# EasyPlanter_V2.net
KiCad netlist of a schematic drawn in EAGLE
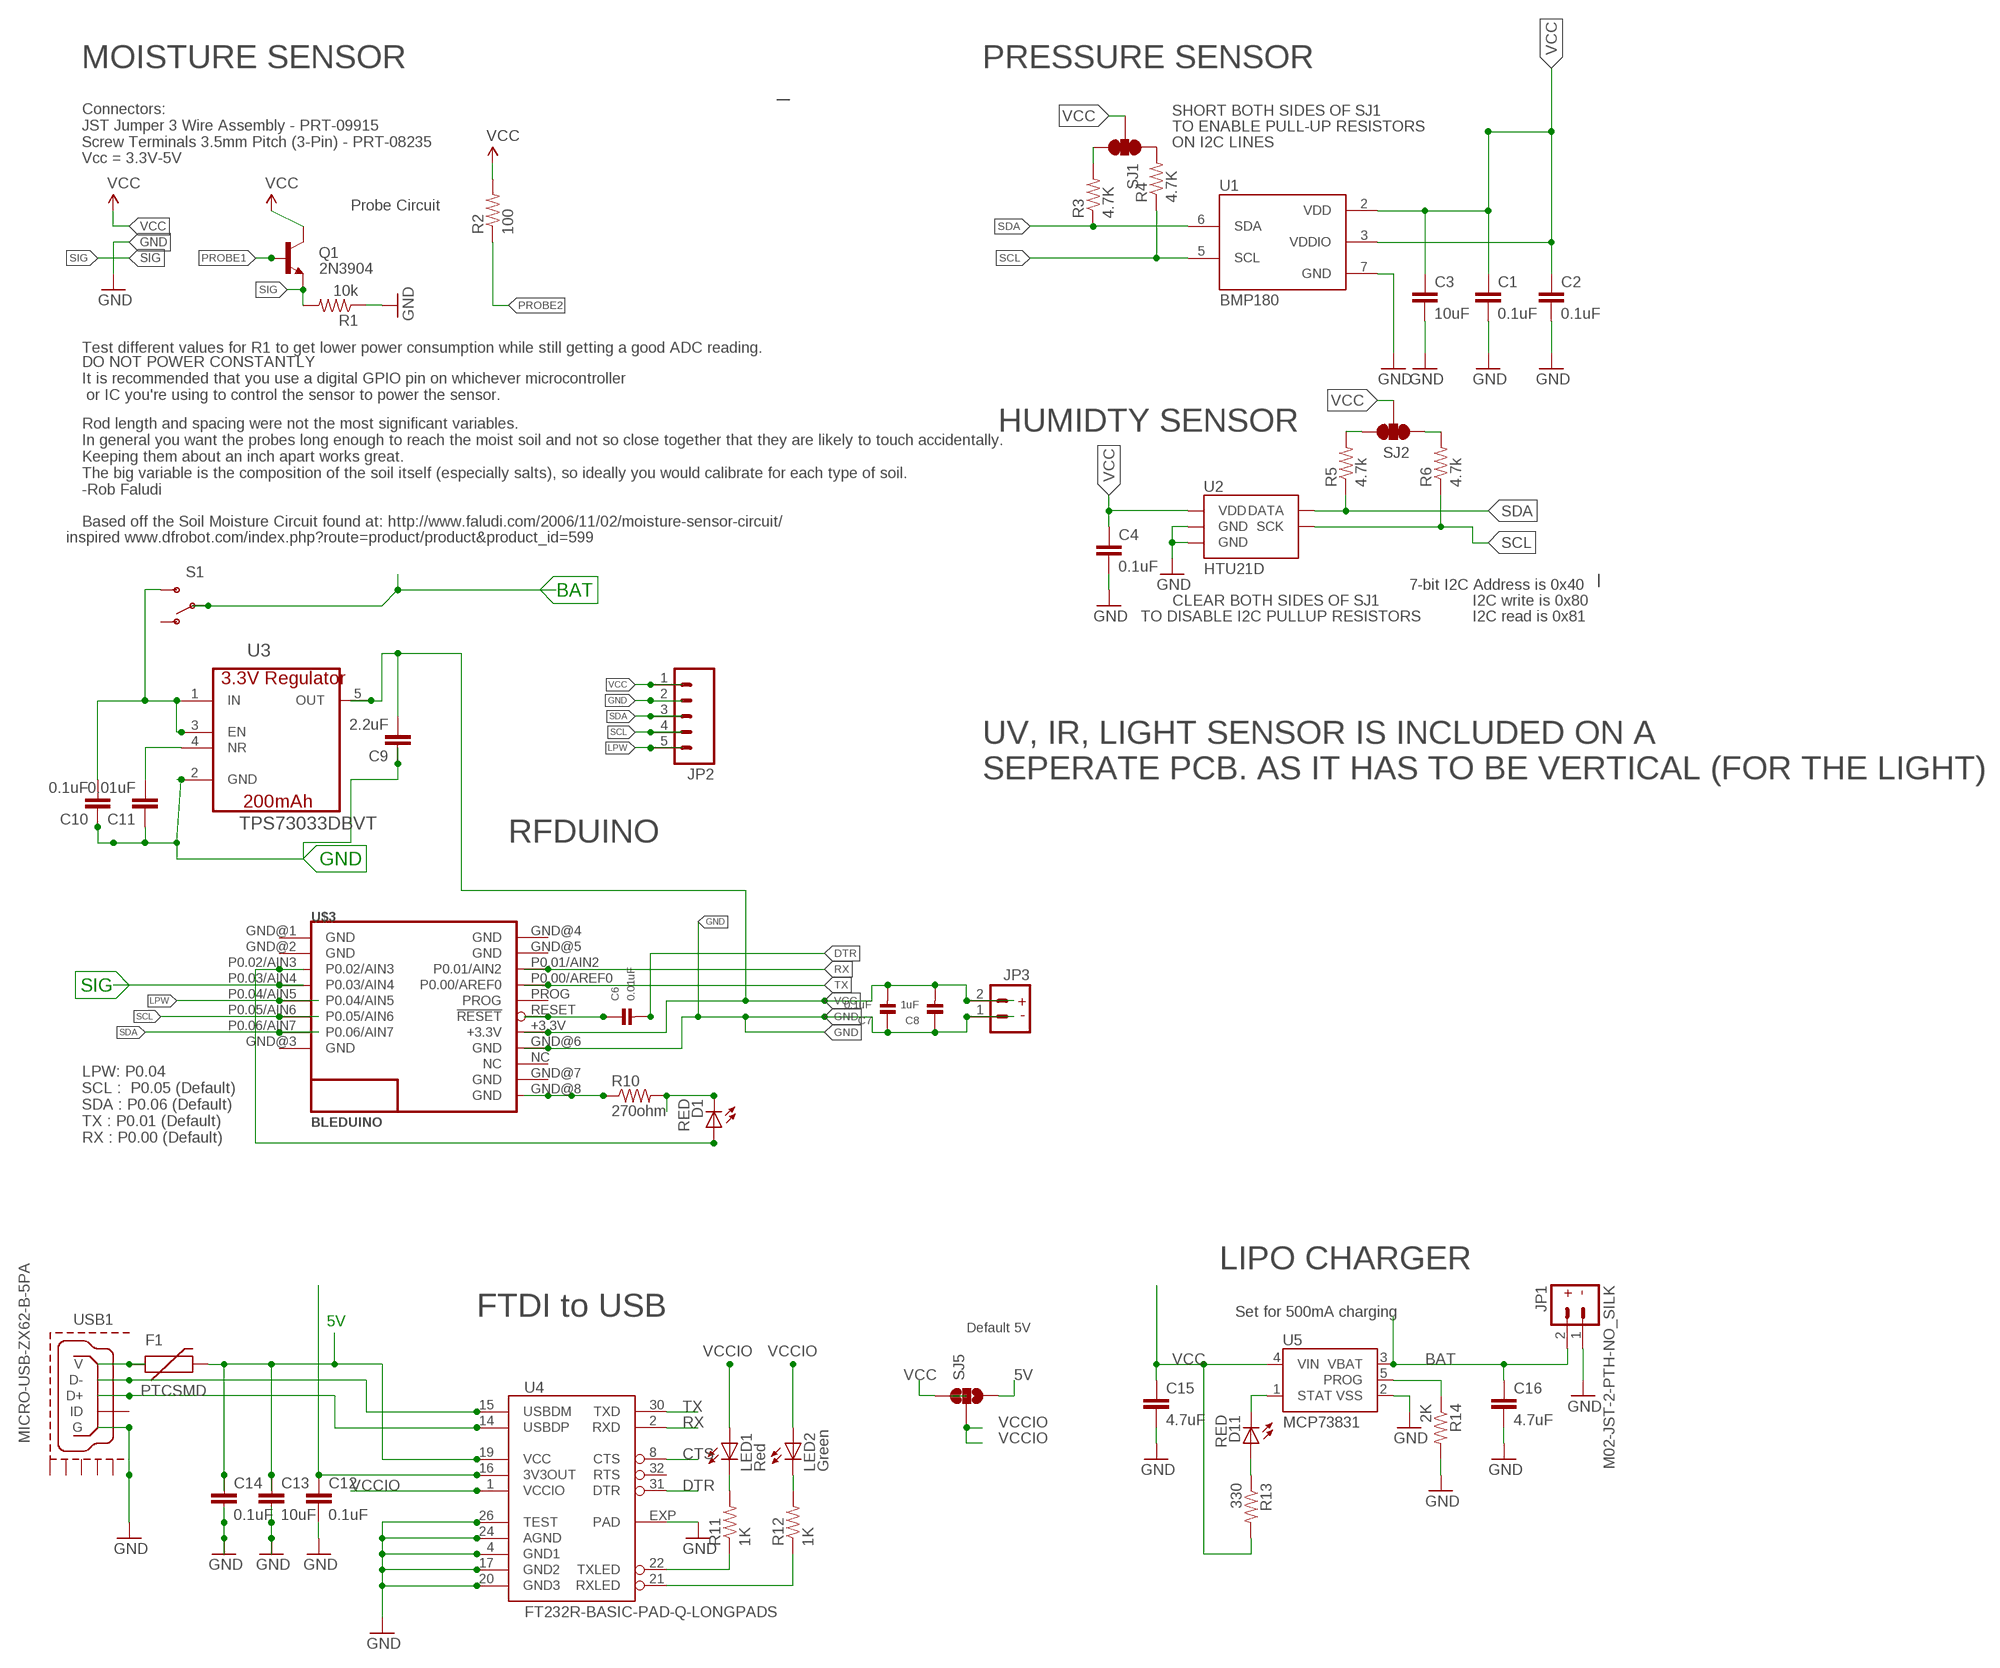
[diagram p0: schematic, sheet 1]

(export (version "E")
  (design (tool "Eeschema 10.0.6"))
  (components
    (comp (ref "C1")
      (value "0.1uF")
      (footprint "eagle-import:0603-CAP")
      (libsource (lib "eagle-import") (part "SparkFun-Capacitors_CAP0603-CAP"))
    )
    (comp (ref "C2")
      (value "0.1uF")
      (footprint "eagle-import:0603-CAP")
      (libsource (lib "eagle-import") (part "SparkFun-Capacitors_CAP0603-CAP"))
    )
    (comp (ref "C3")
      (value "10uF")
      (footprint "eagle-import:0603-CAP")
      (libsource (lib "eagle-import") (part "SparkFun-Capacitors_CAP0603-CAP"))
    )
    (comp (ref "C4")
      (value "0.1uF")
      (footprint "eagle-import:0603-CAP")
      (libsource (lib "eagle-import") (part "CAP0603-CAP"))
    )
    (comp (ref "C6")
      (value "0.01uF")
      (footprint "eagle-import:0402")
      (libsource (lib "eagle-import") (part "CAP_CERAMIC0402"))
    )
    (comp (ref "C7")
      (value "0.1uF")
      (footprint "eagle-import:0402")
      (libsource (lib "eagle-import") (part "CAP_CERAMIC0402"))
    )
    (comp (ref "C8")
      (value "1uF")
      (footprint "eagle-import:0402")
      (libsource (lib "eagle-import") (part "CAP_CERAMIC0402"))
    )
    (comp (ref "C9")
      (value "2.2uF")
      (footprint "eagle-import:0402-CAP")
      (libsource (lib "eagle-import") (part "CAP0402-CAP"))
    )
    (comp (ref "C10")
      (value "0.1uF")
      (footprint "eagle-import:0402-CAP")
      (libsource (lib "eagle-import") (part "CAP0402-CAP"))
    )
    (comp (ref "C11")
      (value "0.01uF")
      (footprint "eagle-import:0402-CAP")
      (libsource (lib "eagle-import") (part "CAP0402-CAP"))
    )
    (comp (ref "C12")
      (value "0.1uF")
      (footprint "eagle-import:0402-CAP")
      (libsource (lib "eagle-import") (part "CAP-0402"))
    )
    (comp (ref "C13")
      (value "10uF")
      (footprint "eagle-import:0402-CAP")
      (libsource (lib "eagle-import") (part "CAP-0402"))
    )
    (comp (ref "C14")
      (value "0.1uF")
      (footprint "eagle-import:0402-CAP")
      (libsource (lib "eagle-import") (part "CAP-0402"))
    )
    (comp (ref "C15")
      (value "4.7uF")
      (footprint "eagle-import:0402-CAP")
      (libsource (lib "eagle-import") (part "CAP0402-CAP"))
    )
    (comp (ref "C16")
      (value "4.7uF")
      (footprint "eagle-import:0402-CAP")
      (libsource (lib "eagle-import") (part "CAP0402-CAP"))
    )
    (comp (ref "D1")
      (value "RED")
      (footprint "eagle-import:LED-0603")
      (libsource (lib "eagle-import") (part "LED-RED0603"))
    )
    (comp (ref "D11")
      (value "RED")
      (footprint "eagle-import:LED-0603")
      (libsource (lib "eagle-import") (part "LED0603"))
    )
    (comp (ref "F1")
      (value "PTCSMD")
      (footprint "eagle-import:PTC-1206")
      (libsource (lib "eagle-import") (part "PTCSMD"))
    )
    (comp (ref "JP1")
      (value "M02-JST-2-PTH-NO_SILK")
      (footprint "eagle-import:JST-2-PTH-NS")
      (libsource (lib "eagle-import") (part "M02-JST-2-PTH-NO_SILK"))
    )
    (comp (ref "JP2")
      (value "M05PTH")
      (footprint "eagle-import:1X05")
      (libsource (lib "eagle-import") (part "M05PTH"))
    )
    (comp (ref "JP3")
      (value "M02-JST-2-PTH-NO_SILK")
      (footprint "eagle-import:JST-2-PTH-NS")
      (libsource (lib "eagle-import") (part "M02-JST-2-PTH-NO_SILK"))
    )
    (comp (ref "LED1")
      (value "Red")
      (footprint "eagle-import:LED-0603")
      (libsource (lib "eagle-import") (part "akafugu_LED0603"))
    )
    (comp (ref "LED2")
      (value "Green")
      (footprint "eagle-import:LED-0603")
      (libsource (lib "eagle-import") (part "akafugu_LED0603"))
    )
    (comp (ref "Q1")
      (value "2N3904")
      (footprint "eagle-import:SOT23-3")
      (libsource (lib "eagle-import") (part "TRANSISTOR_NPNMMBT2222A"))
    )
    (comp (ref "R1")
      (value "10k")
      (footprint "eagle-import:0603-RES")
      (libsource (lib "eagle-import") (part "100OHM-1/4W-5%(0603)"))
    )
    (comp (ref "R2")
      (value "100")
      (footprint "eagle-import:0603-RES")
      (libsource (lib "eagle-import") (part "100OHM-1/4W-5%(0603)"))
    )
    (comp (ref "R3")
      (value "4.7K")
      (footprint "eagle-import:0603-RES")
      (libsource (lib "eagle-import") (part "SparkFun-Passives_RESISTOR0603-RES"))
    )
    (comp (ref "R4")
      (value "4.7K")
      (footprint "eagle-import:0603-RES")
      (libsource (lib "eagle-import") (part "SparkFun-Passives_RESISTOR0603-RES"))
    )
    (comp (ref "R5")
      (value "4.7k")
      (footprint "eagle-import:0603-RES")
      (libsource (lib "eagle-import") (part "RESISTOR0603-RES"))
    )
    (comp (ref "R6")
      (value "4.7k")
      (footprint "eagle-import:0603-RES")
      (libsource (lib "eagle-import") (part "RESISTOR0603-RES"))
    )
    (comp (ref "R10")
      (value "270ohm")
      (footprint "eagle-import:0402-RES")
      (libsource (lib "eagle-import") (part "SparkFun-Passives_RESISTOR0402-RES"))
    )
    (comp (ref "R11")
      (value "1K")
      (footprint "eagle-import:R0402")
      (libsource (lib "eagle-import") (part "RESISTOR-0402"))
    )
    (comp (ref "R12")
      (value "1K")
      (footprint "eagle-import:R0402")
      (libsource (lib "eagle-import") (part "RESISTOR-0402"))
    )
    (comp (ref "R13")
      (value "330")
      (footprint "eagle-import:0402-RES")
      (libsource (lib "eagle-import") (part "RESISTOR0402-RES"))
    )
    (comp (ref "R14")
      (value "2K")
      (footprint "eagle-import:0402-RES")
      (libsource (lib "eagle-import") (part "RESISTOR0402-RES"))
    )
    (comp (ref "S1")
      (value "SWITCH-SPDT-SMD-A")
      (footprint "eagle-import:SWITCH-SPST-SMD-A")
      (libsource (lib "eagle-import") (part "SWITCH-SPDT-SMD-A"))
    )
    (comp (ref "SJ1")
      (value "SOLDERJUMPER_2WAYPASTE1&2&3")
      (footprint "eagle-import:SJ_3_PASTE1&2&3")
      (libsource (lib "eagle-import") (part "SOLDERJUMPER_2WAYPASTE1&2&3"))
    )
    (comp (ref "SJ2")
      (value "SOLDERJUMPER_2WAYPASTE1&2&3")
      (footprint "eagle-import:SJ_3_PASTE1&2&3")
      (libsource (lib "eagle-import") (part "SOLDERJUMPER_2WAYPASTE1&2&3"))
    )
    (comp (ref "SJ5")
      (value "SOLDERJUMPER_2WAY-LEFT-BRIDGED")
      (footprint "eagle-import:SJ-3-LEFT")
      (libsource (lib "eagle-import") (part "SOLDERJUMPER_2WAY-LEFT-BRIDGED"))
    )
    (comp (ref "U$3")
      (value "BLEDUINO")
      (footprint "eagle-import:BLEDUINO")
      (libsource (lib "eagle-import") (part "BLEDUINO"))
    )
    (comp (ref "U1")
      (value "BMP180")
      (footprint "eagle-import:BMP180")
      (libsource (lib "eagle-import") (part "BMP180"))
    )
    (comp (ref "U2")
      (value "HTU21D")
      (footprint "eagle-import:HTU21D")
      (libsource (lib "eagle-import") (part "HTU21DSMD"))
    )
    (comp (ref "U3")
      (value "TPS73033DBVT")
      (footprint "eagle-import:SOT95P290X145-5N")
      (libsource (lib "eagle-import") (part "TPS73033DBVT"))
    )
    (comp (ref "U4")
      (value "FT232R-BASIC-PAD-Q-LONGPADS")
      (footprint "eagle-import:QFN32-LONG")
      (libsource (lib "eagle-import") (part "FT232R-BASIC-PAD-Q-LONGPADS"))
    )
    (comp (ref "U5")
      (value "MCP73831")
      (footprint "eagle-import:SOT23-5")
      (libsource (lib "eagle-import") (part "MCP73831"))
    )
    (comp (ref "USB1")
      (value "MICRO-USB-ZX62-B-5PA")
      (footprint "eagle-import:ZX62-B-5PA")
      (libsource (lib "eagle-import") (part "MICRO-USB-ZX62-B-5PA"))
    )
  )
  (nets
    (net (code "1") (name "/5V") (class "Default")
      (node (ref "C13") (pin "1") (pinfunction "1_1") (pintype "passive"))
      (node (ref "C14") (pin "1") (pinfunction "1_1") (pintype "passive"))
      (node (ref "F1") (pin "2") (pinfunction "2_2") (pintype "bidirectional"))
      (node (ref "SJ5") (pin "3") (pinfunction "3_3") (pintype "passive"))
      (node (ref "U4") (pin "19") (pinfunction "VCC_19") (pintype "power_in"))
    )
    (net (code "2") (name "/CTS") (class "Default")
      (node (ref "U4") (pin "8") (pinfunction "CTS_8") (pintype "bidirectional"))
    )
    (net (code "3") (name "/GND1") (class "Default")
      (node (ref "USB1") (pin "GND@1") (pinfunction "GND1_GND@1") (pintype "power_in"))
    )
    (net (code "4") (name "/GND2") (class "Default")
      (node (ref "USB1") (pin "GND@2") (pinfunction "GND2_GND@2") (pintype "power_in"))
    )
    (net (code "5") (name "/GND3") (class "Default")
      (node (ref "USB1") (pin "GND@3") (pinfunction "GND3_GND@3") (pintype "power_in"))
    )
    (net (code "6") (name "/GND4") (class "Default")
      (node (ref "USB1") (pin "GND@4") (pinfunction "GND4_GND@4") (pintype "power_in"))
    )
    (net (code "7") (name "/GND5") (class "Default")
      (node (ref "USB1") (pin "GND@5") (pinfunction "GND5_GND@5") (pintype "power_in"))
    )
    (net (code "8") (name "/VCCIO") (class "Default")
      (node (ref "LED1") (pin "A") (pinfunction "A_A") (pintype "passive"))
      (node (ref "LED2") (pin "A") (pinfunction "A_A") (pintype "passive"))
      (node (ref "SJ5") (pin "2") (pinfunction "2_2") (pintype "passive"))
      (node (ref "U4") (pin "1") (pinfunction "VCCIO_1") (pintype "power_in"))
    )
    (net (code "9") (name "BAT") (class "Default")
      (node (ref "C16") (pin "1") (pinfunction "1_1") (pintype "passive"))
      (node (ref "JP1") (pin "2") (pinfunction "2_2") (pintype "passive"))
      (node (ref "S1") (pin "2") (pinfunction "P_2") (pintype "passive"))
      (node (ref "U5") (pin "3") (pinfunction "VBAT_3") (pintype "power_in"))
    )
    (net (code "10") (name "DTR") (class "Default")
      (node (ref "C6") (pin "2") (pinfunction "P$2_2") (pintype "passive"))
      (node (ref "U4") (pin "31") (pinfunction "DTR_31") (pintype "bidirectional"))
    )
    (net (code "11") (name "GND") (class "Default")
      (node (ref "C1") (pin "2") (pinfunction "2_2") (pintype "passive"))
      (node (ref "C10") (pin "1") (pinfunction "1_1") (pintype "passive"))
      (node (ref "C11") (pin "1") (pinfunction "1_1") (pintype "passive"))
      (node (ref "C12") (pin "2") (pinfunction "2_2") (pintype "passive"))
      (node (ref "C13") (pin "2") (pinfunction "2_2") (pintype "passive"))
      (node (ref "C14") (pin "2") (pinfunction "2_2") (pintype "passive"))
      (node (ref "C15") (pin "2") (pinfunction "2_2") (pintype "passive"))
      (node (ref "C16") (pin "2") (pinfunction "2_2") (pintype "passive"))
      (node (ref "C2") (pin "2") (pinfunction "2_2") (pintype "passive"))
      (node (ref "C3") (pin "2") (pinfunction "2_2") (pintype "passive"))
      (node (ref "C4") (pin "2") (pinfunction "2_2") (pintype "passive"))
      (node (ref "C7") (pin "1") (pinfunction "P$1_1") (pintype "passive"))
      (node (ref "C8") (pin "1") (pinfunction "P$1_1") (pintype "passive"))
      (node (ref "C9") (pin "1") (pinfunction "1_1") (pintype "passive"))
      (node (ref "JP1") (pin "1") (pinfunction "1_1") (pintype "passive"))
      (node (ref "JP2") (pin "2") (pinfunction "2_2") (pintype "passive"))
      (node (ref "JP3") (pin "1") (pinfunction "1_1") (pintype "passive"))
      (node (ref "R1") (pin "1") (pinfunction "1_1") (pintype "passive"))
      (node (ref "R14") (pin "2") (pinfunction "2_2") (pintype "passive"))
      (node (ref "U$3") (pin "GND@6") (pinfunction "GND_GND@6") (pintype "bidirectional"))
      (node (ref "U1") (pin "7") (pinfunction "GND_7") (pintype "power_in"))
      (node (ref "U2") (pin "7") (pinfunction "GND_7") (pintype "power_in"))
      (node (ref "U2") (pin "GND") (pinfunction "GND_GND") (pintype "power_in"))
      (node (ref "U3") (pin "2") (pinfunction "GND_2") (pintype "passive"))
      (node (ref "U4") (pin "17") (pinfunction "GND2_17") (pintype "power_in"))
      (node (ref "U4") (pin "20") (pinfunction "GND3_20") (pintype "power_in"))
      (node (ref "U4") (pin "24") (pinfunction "AGND_24") (pintype "power_in"))
      (node (ref "U4") (pin "26") (pinfunction "TEST_26") (pintype "input"))
      (node (ref "U4") (pin "4") (pinfunction "GND1_4") (pintype "power_in"))
      (node (ref "U4") (pin "EXP") (pinfunction "PAD_EXP") (pintype "bidirectional"))
      (node (ref "U5") (pin "2") (pinfunction "VSS_2") (pintype "power_in"))
      (node (ref "USB1") (pin "5") (pinfunction "G_5") (pintype "input"))
      (node (ref "USB1") (pin "GND@6") (pinfunction "GND6_GND@6") (pintype "power_in"))
    )
    (net (code "12") (name "LPW") (class "Default")
      (node (ref "JP2") (pin "5") (pinfunction "5_5") (pintype "passive"))
      (node (ref "U$3") (pin "P0.04/AIN5") (pinfunction "P0.04/AIN5_P0.04/AIN5") (pintype "bidirectional"))
    )
    (net (code "13") (name "Net-(C6-P$1)") (class "Default")
      (node (ref "C6") (pin "1") (pinfunction "P$1_1") (pintype "passive"))
      (node (ref "U$3") (pin "RESET") (pinfunction "~{RESET}_RESET") (pintype "bidirectional"))
    )
    (net (code "14") (name "Net-(D1-PadA)") (class "Default")
      (node (ref "D1") (pin "A") (pinfunction "A_A") (pintype "passive"))
      (node (ref "U$3") (pin "P0.02/AIN3") (pinfunction "P0.02/AIN3_P0.02/AIN3") (pintype "bidirectional"))
    )
    (net (code "15") (name "Net-(D1-PadC)") (class "Default")
      (node (ref "D1") (pin "C") (pinfunction "C_C") (pintype "passive"))
      (node (ref "R10") (pin "2") (pinfunction "2_2") (pintype "passive"))
    )
    (net (code "16") (name "Net-(D11-PadA)") (class "Default")
      (node (ref "D11") (pin "A") (pinfunction "A_A") (pintype "passive"))
      (node (ref "R13") (pin "1") (pinfunction "1_1") (pintype "passive"))
    )
    (net (code "17") (name "Net-(LED1-PadC)") (class "Default")
      (node (ref "LED1") (pin "C") (pinfunction "C_C") (pintype "passive"))
      (node (ref "R11") (pin "2") (pinfunction "2_2") (pintype "passive"))
    )
    (net (code "18") (name "Net-(LED2-PadC)") (class "Default")
      (node (ref "LED2") (pin "C") (pinfunction "C_C") (pintype "passive"))
      (node (ref "R12") (pin "2") (pinfunction "2_2") (pintype "passive"))
    )
    (net (code "19") (name "Net-(R3-Pad2)") (class "Default")
      (node (ref "R3") (pin "2") (pinfunction "2_2") (pintype "passive"))
      (node (ref "SJ1") (pin "3") (pinfunction "3_3") (pintype "passive"))
    )
    (net (code "20") (name "Net-(R4-Pad2)") (class "Default")
      (node (ref "R4") (pin "2") (pinfunction "2_2") (pintype "passive"))
      (node (ref "SJ1") (pin "1") (pinfunction "1_1") (pintype "passive"))
    )
    (net (code "21") (name "Net-(R5-Pad2)") (class "Default")
      (node (ref "R5") (pin "2") (pinfunction "2_2") (pintype "passive"))
      (node (ref "SJ2") (pin "3") (pinfunction "3_3") (pintype "passive"))
    )
    (net (code "22") (name "Net-(R6-Pad2)") (class "Default")
      (node (ref "R6") (pin "2") (pinfunction "2_2") (pintype "passive"))
      (node (ref "SJ2") (pin "1") (pinfunction "1_1") (pintype "passive"))
    )
    (net (code "23") (name "Net-(R10-Pad1)") (class "Default")
      (node (ref "R10") (pin "1") (pinfunction "1_1") (pintype "passive"))
      (node (ref "U$3") (pin "GND@8") (pinfunction "GND_GND@8") (pintype "bidirectional"))
    )
    (net (code "24") (name "Net-(S1-S)") (class "Default")
      (node (ref "C10") (pin "2") (pinfunction "2_2") (pintype "passive"))
      (node (ref "S1") (pin "3") (pinfunction "S_3") (pintype "passive"))
      (node (ref "U3") (pin "1") (pinfunction "IN_1") (pintype "input"))
      (node (ref "U3") (pin "3") (pinfunction "EN_3") (pintype "input"))
    )
    (net (code "25") (name "Net-(U3-NR)") (class "Default")
      (node (ref "C11") (pin "2") (pinfunction "2_2") (pintype "passive"))
      (node (ref "U3") (pin "4") (pinfunction "NR_4") (pintype "input"))
    )
    (net (code "26") (name "Net-(U4-RXLED)") (class "Default")
      (node (ref "R12") (pin "1") (pinfunction "1_1") (pintype "passive"))
      (node (ref "U4") (pin "21") (pinfunction "RXLED_21") (pintype "bidirectional"))
    )
    (net (code "27") (name "Net-(U4-TXLED)") (class "Default")
      (node (ref "R11") (pin "1") (pinfunction "1_1") (pintype "passive"))
      (node (ref "U4") (pin "22") (pinfunction "TXLED_22") (pintype "bidirectional"))
    )
    (net (code "28") (name "Net-(U4-USBDM)") (class "Default")
      (node (ref "U4") (pin "15") (pinfunction "USBDM_15") (pintype "bidirectional"))
      (node (ref "USB1") (pin "2") (pinfunction "D-_2") (pintype "input"))
    )
    (net (code "29") (name "Net-(U4-USBDP)") (class "Default")
      (node (ref "U4") (pin "14") (pinfunction "USBDP_14") (pintype "bidirectional"))
      (node (ref "USB1") (pin "3") (pinfunction "D+_3") (pintype "input"))
    )
    (net (code "30") (name "Net-(U5-PROG)") (class "Default")
      (node (ref "R14") (pin "1") (pinfunction "1_1") (pintype "passive"))
      (node (ref "U5") (pin "5") (pinfunction "PROG_5") (pintype "input"))
    )
    (net (code "31") (name "Net-(U5-STAT)") (class "Default")
      (node (ref "D11") (pin "C") (pinfunction "C_C") (pintype "passive"))
      (node (ref "U5") (pin "1") (pinfunction "STAT_1") (pintype "output"))
    )
    (net (code "32") (name "Net-(USB1-V)") (class "Default")
      (node (ref "F1") (pin "1") (pinfunction "1_1") (pintype "bidirectional"))
      (node (ref "USB1") (pin "1") (pinfunction "V_1") (pintype "input"))
    )
    (net (code "33") (name "PROBE1") (class "Default")
      (node (ref "Q1") (pin "1") (pinfunction "B_1") (pintype "passive"))
    )
    (net (code "34") (name "PROBE2") (class "Default")
      (node (ref "R2") (pin "1") (pinfunction "1_1") (pintype "passive"))
    )
    (net (code "35") (name "RX") (class "Default")
      (node (ref "U$3") (pin "P0.01/AIN2") (pinfunction "P0.01/AIN2_P0.01/AIN2") (pintype "bidirectional"))
      (node (ref "U4") (pin "2") (pinfunction "RXD_2") (pintype "input"))
    )
    (net (code "36") (name "SCL") (class "Default")
      (node (ref "JP2") (pin "4") (pinfunction "4_4") (pintype "passive"))
      (node (ref "R4") (pin "1") (pinfunction "1_1") (pintype "passive"))
      (node (ref "R6") (pin "1") (pinfunction "1_1") (pintype "passive"))
      (node (ref "U$3") (pin "P0.05/AIN6") (pinfunction "P0.05/AIN6_P0.05/AIN6") (pintype "bidirectional"))
      (node (ref "U1") (pin "5") (pinfunction "SCL_5") (pintype "input"))
      (node (ref "U2") (pin "SCK") (pinfunction "SCK_SCK") (pintype "input"))
    )
    (net (code "37") (name "SDA") (class "Default")
      (node (ref "JP2") (pin "3") (pinfunction "3_3") (pintype "passive"))
      (node (ref "R3") (pin "1") (pinfunction "1_1") (pintype "passive"))
      (node (ref "R5") (pin "1") (pinfunction "1_1") (pintype "passive"))
      (node (ref "U$3") (pin "P0.06/AIN7") (pinfunction "P0.06/AIN7_P0.06/AIN7") (pintype "bidirectional"))
      (node (ref "U1") (pin "6") (pinfunction "SDA_6") (pintype "bidirectional"))
      (node (ref "U2") (pin "DATA") (pinfunction "DATA_DATA") (pintype "bidirectional"))
    )
    (net (code "38") (name "SIG") (class "Default")
      (node (ref "Q1") (pin "2") (pinfunction "E_2") (pintype "passive"))
      (node (ref "R1") (pin "2") (pinfunction "2_2") (pintype "passive"))
      (node (ref "U$3") (pin "P0.03/AIN4") (pinfunction "P0.03/AIN4_P0.03/AIN4") (pintype "bidirectional"))
    )
    (net (code "39") (name "TX") (class "Default")
      (node (ref "U$3") (pin "P0.00/AREF0") (pinfunction "P0.00/AREF0_P0.00/AREF0") (pintype "bidirectional"))
      (node (ref "U4") (pin "30") (pinfunction "TXD_30") (pintype "output"))
    )
    (net (code "40") (name "VCC") (class "Default")
      (node (ref "C1") (pin "1") (pinfunction "1_1") (pintype "passive"))
      (node (ref "C12") (pin "1") (pinfunction "1_1") (pintype "passive"))
      (node (ref "C15") (pin "1") (pinfunction "1_1") (pintype "passive"))
      (node (ref "C2") (pin "1") (pinfunction "1_1") (pintype "passive"))
      (node (ref "C3") (pin "1") (pinfunction "1_1") (pintype "passive"))
      (node (ref "C4") (pin "1") (pinfunction "1_1") (pintype "passive"))
      (node (ref "C7") (pin "2") (pinfunction "P$2_2") (pintype "passive"))
      (node (ref "C8") (pin "2") (pinfunction "P$2_2") (pintype "passive"))
      (node (ref "C9") (pin "2") (pinfunction "2_2") (pintype "passive"))
      (node (ref "JP2") (pin "1") (pinfunction "1_1") (pintype "passive"))
      (node (ref "JP3") (pin "2") (pinfunction "2_2") (pintype "passive"))
      (node (ref "Q1") (pin "3") (pinfunction "C_3") (pintype "passive"))
      (node (ref "R13") (pin "2") (pinfunction "2_2") (pintype "passive"))
      (node (ref "R2") (pin "2") (pinfunction "2_2") (pintype "passive"))
      (node (ref "SJ1") (pin "2") (pinfunction "2_2") (pintype "passive"))
      (node (ref "SJ2") (pin "2") (pinfunction "2_2") (pintype "passive"))
      (node (ref "SJ5") (pin "1") (pinfunction "1_1") (pintype "passive"))
      (node (ref "U$3") (pin "+3.3V") (pinfunction "+3.3V_+3.3V") (pintype "bidirectional"))
      (node (ref "U1") (pin "2") (pinfunction "VDD_2") (pintype "power_in"))
      (node (ref "U1") (pin "3") (pinfunction "VDDIO_3") (pintype "power_in"))
      (node (ref "U2") (pin "VDD") (pinfunction "VDD_VDD") (pintype "power_in"))
      (node (ref "U3") (pin "5") (pinfunction "OUT_5") (pintype "output"))
      (node (ref "U4") (pin "16") (pinfunction "3V3OUT_16") (pintype "output"))
      (node (ref "U5") (pin "4") (pinfunction "VIN_4") (pintype "power_in"))
    )
    (net (code "41") (name "unconnected-(S1-O-Pad1)") (class "Default")
      (node (ref "S1") (pin "1") (pinfunction "O_1") (pintype "passive"))
    )
    (net (code "42") (name "unconnected-(U$3-GND-PadGND@1)") (class "Default")
      (node (ref "U$3") (pin "GND@1") (pinfunction "GND_GND@1") (pintype "bidirectional"))
    )
    (net (code "43") (name "unconnected-(U$3-GND-PadGND@2)") (class "Default")
      (node (ref "U$3") (pin "GND@2") (pinfunction "GND_GND@2") (pintype "bidirectional"))
    )
    (net (code "44") (name "unconnected-(U$3-GND-PadGND@3)") (class "Default")
      (node (ref "U$3") (pin "GND@3") (pinfunction "GND_GND@3") (pintype "bidirectional"))
    )
    (net (code "45") (name "unconnected-(U$3-GND-PadGND@4)") (class "Default")
      (node (ref "U$3") (pin "GND@4") (pinfunction "GND_GND@4") (pintype "bidirectional"))
    )
    (net (code "46") (name "unconnected-(U$3-GND-PadGND@5)") (class "Default")
      (node (ref "U$3") (pin "GND@5") (pinfunction "GND_GND@5") (pintype "bidirectional"))
    )
    (net (code "47") (name "unconnected-(U$3-GND-PadGND@7)") (class "Default")
      (node (ref "U$3") (pin "GND@7") (pinfunction "GND_GND@7") (pintype "bidirectional"))
    )
    (net (code "48") (name "unconnected-(U$3-PadNC)") (class "Default")
      (node (ref "U$3") (pin "NC") (pinfunction "NC_NC") (pintype "no_connect"))
    )
    (net (code "49") (name "unconnected-(U$3-PadPROG)") (class "Default")
      (node (ref "U$3") (pin "PROG") (pinfunction "PROG_PROG") (pintype "bidirectional"))
    )
    (net (code "50") (name "unconnected-(U4-RTS-Pad32)") (class "Default")
      (node (ref "U4") (pin "32") (pinfunction "RTS_32") (pintype "bidirectional"))
    )
    (net (code "51") (name "unconnected-(USB1-ID-Pad4)") (class "Default")
      (node (ref "USB1") (pin "4") (pinfunction "ID_4") (pintype "input"))
    )
  )
)
